# APC1_EPS.net
KiCad netlist of a schematic drawn in Altium Designer
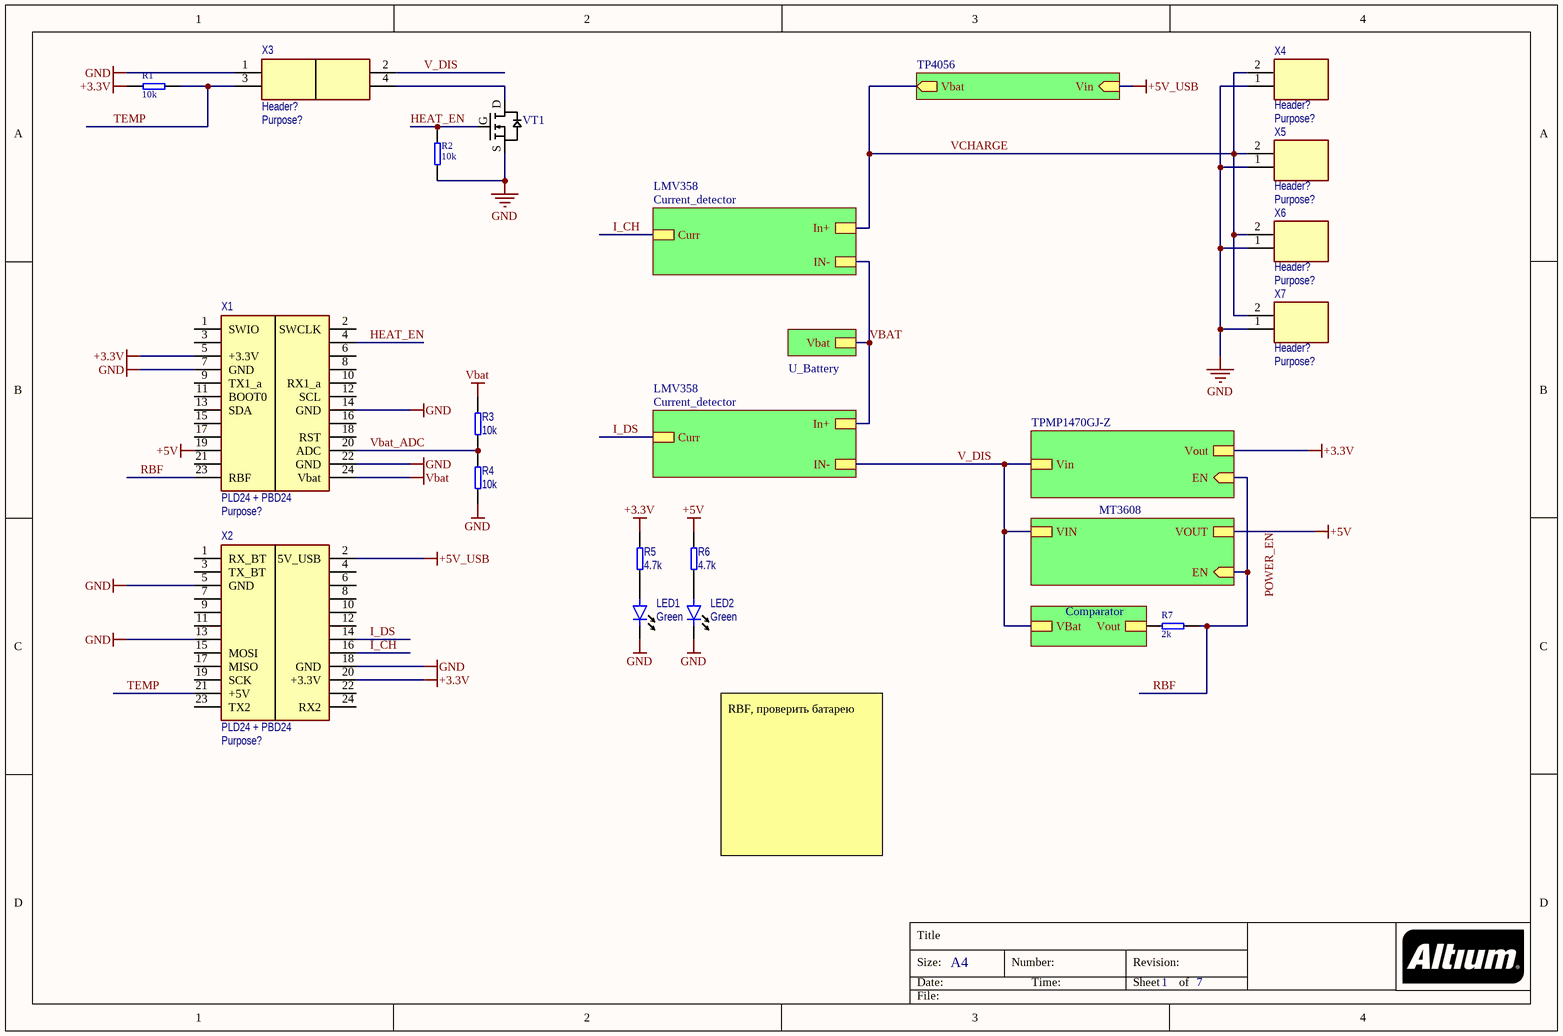
[diagram p0: APC1_EPS.SchDoc]

(export (version "E")
  (design (tool "Eeschema 10.0.6"))
  (components
    (comp (ref "LED1")
      (value "Green")
      (footprint "LED 0603")
      (description "Light Emittering Diode")
      (fields (field (name "Comment") "LED 0603 Green"))
      (libsource (lib "!main") (part "LED"))
    )
    (comp (ref "LED2")
      (value "Green")
      (footprint "LED 0603")
      (description "Light Emittering Diode")
      (fields (field (name "Comment") "LED 0603 Green"))
      (libsource (lib "!main") (part "LED"))
    )
    (comp (ref "R1")
      (value "10k")
      (footprint "RES 0402")
      (description "Resistor")
      (fields (field (name "Comment") "RES 0402 10k"))
      (libsource (lib "!main") (part "!Resistor"))
    )
    (comp (ref "R2")
      (value "10k")
      (footprint "RES 0402")
      (description "Resistor")
      (fields (field (name "Comment") "RES 0402 10k"))
      (libsource (lib "!main") (part "!Resistor"))
    )
    (comp (ref "R3")
      (value "10k")
      (footprint "RES 0402")
      (description "Resistor")
      (fields (field (name "Comment") "RES 0402 10k"))
      (libsource (lib "!main") (part "!Resistor"))
    )
    (comp (ref "R4")
      (value "10k")
      (footprint "RES 0402")
      (description "Resistor")
      (fields (field (name "Comment") "RES 0402 10k"))
      (libsource (lib "!main") (part "!Resistor"))
    )
    (comp (ref "R5")
      (value "4.7k")
      (footprint "RES 0402")
      (description "Resistor")
      (fields (field (name "Comment") "RES 0402 4.7k"))
      (libsource (lib "!main") (part "!Resistor"))
    )
    (comp (ref "R6")
      (value "4.7k")
      (footprint "RES 0402")
      (description "Resistor")
      (fields (field (name "Comment") "RES 0402 4.7k"))
      (libsource (lib "!main") (part "!Resistor"))
    )
    (comp (ref "R7")
      (value "2k")
      (footprint "RES 0402")
      (description "Resistor")
      (fields (field (name "Comment") "RES 0402 2k"))
      (libsource (lib "!main") (part "!Resistor"))
    )
    (comp (ref "VT1")
      (value "AO3400A")
      (footprint "SOT23-3")
      (description "generic N mosfet")
      (libsource (lib "transistors") (part "!Generic N MOSFET"))
    )
    (comp (ref "X1")
      (value "PLD24 + PBD24")
      (footprint "PICOSAT_CNN")
      (description "10x2 header")
      (fields (field (name "PURPOSE") "Purpose?"))
      (libsource (lib "connectors") (part "Header 2x12"))
    )
    (comp (ref "X2")
      (value "PLD24 + PBD24")
      (footprint "PICOSAT_CNN")
      (description "10x2 header")
      (fields (field (name "PURPOSE") "Purpose?"))
      (libsource (lib "connectors") (part "Header 2x12"))
    )
    (comp (ref "X3")
      (value "Header?")
      (footprint "PBD-4-2.54")
      (description "2x2 header")
      (fields (field (name "PURPOSE") "Purpose?"))
      (libsource (lib "connectors") (part "Header 2x2"))
    )
    (comp (ref "X4")
      (value "Header?")
      (footprint "ZH-2")
      (description "2x1 header")
      (fields (field (name "PURPOSE") "Purpose?"))
      (libsource (lib "connectors") (part "Header 1x2"))
    )
    (comp (ref "X5")
      (value "Header?")
      (footprint "ZH-2")
      (description "2x1 header")
      (fields (field (name "PURPOSE") "Purpose?"))
      (libsource (lib "connectors") (part "Header 1x2"))
    )
    (comp (ref "X6")
      (value "Header?")
      (footprint "ZH-2")
      (description "2x1 header")
      (fields (field (name "PURPOSE") "Purpose?"))
      (libsource (lib "connectors") (part "Header 1x2"))
    )
    (comp (ref "X7")
      (value "Header?")
      (footprint "ZH-2")
      (description "2x1 header")
      (fields (field (name "PURPOSE") "Purpose?"))
      (libsource (lib "connectors") (part "Header 1x2"))
    )
  )
  (nets
    (net (code "1") (name "+3.3V") (class "Default")
      (node (ref "R1") (pin "1") (pinfunction "11_1") (pintype "passive"))
      (node (ref "R5") (pin "2") (pinfunction "12_2") (pintype "passive"))
      (node (ref "X1") (pin "5") (pinfunction "+3.3V_5") (pintype "passive"))
      (node (ref "X2") (pin "20") (pinfunction "ADC_20") (pintype "passive"))
    )
    (net (code "2") (name "+5V") (class "Default")
      (node (ref "R6") (pin "2") (pinfunction "12_2") (pintype "passive"))
      (node (ref "X1") (pin "19") (pintype "passive"))
    )
    (net (code "3") (name "+5V_USB") (class "Default")
      (node (ref "X2") (pin "2") (pinfunction "SWCLK_2") (pintype "passive"))
    )
    (net (code "4") (name "/HEAT_EN") (class "Default")
      (node (ref "R2") (pin "2") (pinfunction "12_2") (pintype "passive"))
      (node (ref "VT1") (pin "G2") (pintype "passive"))
      (node (ref "X1") (pin "4") (pintype "passive"))
    )
    (net (code "5") (name "/I_CH") (class "Default") (node (ref "X2") (pin "16") (pintype "passive")))
    (net (code "6") (name "/I_DS") (class "Default")
      (node (ref "X2") (pin "14") (pinfunction "GND_14") (pintype "passive"))
    )
    (net (code "7") (name "/RBF") (class "Default")
      (node (ref "R7") (pin "2") (pinfunction "12_2") (pintype "passive"))
      (node (ref "X1") (pin "23") (pinfunction "RBF_23") (pintype "passive"))
    )
    (net (code "8") (name "/TEMP") (class "Default")
      (node (ref "R1") (pin "2") (pinfunction "12_2") (pintype "passive"))
      (node (ref "X2") (pin "21") (pintype "passive"))
      (node (ref "X3") (pin "3") (pinfunction "6_3") (pintype "passive"))
    )
    (net (code "10") (name "/VCHARGE") (class "Default")
      (node (ref "X4") (pin "2") (pinfunction "2_2") (pintype "passive"))
      (node (ref "X5") (pin "2") (pinfunction "2_2") (pintype "passive"))
      (node (ref "X6") (pin "2") (pinfunction "2_2") (pintype "passive"))
      (node (ref "X7") (pin "2") (pinfunction "2_2") (pintype "passive"))
    )
    (net (code "11") (name "/V_DIS") (class "Default")
      (node (ref "X3") (pin "2") (pinfunction "3_2") (pintype "passive"))
    )
    (net (code "12") (name "/Vbat_ADC") (class "Default")
      (node (ref "R3") (pin "1") (pinfunction "11_1") (pintype "passive"))
      (node (ref "R4") (pin "2") (pinfunction "12_2") (pintype "passive"))
      (node (ref "X1") (pin "20") (pinfunction "ADC_20") (pintype "passive"))
    )
    (net (code "13") (name "/Vout") (class "Default")
      (node (ref "R7") (pin "1") (pinfunction "11_1") (pintype "passive"))
    )
    (net (code "14") (name "GND") (class "Default")
      (node (ref "LED1") (pin "2") (pinfunction "Cathode_2") (pintype "passive"))
      (node (ref "LED2") (pin "2") (pinfunction "Cathode_2") (pintype "passive"))
      (node (ref "R2") (pin "1") (pinfunction "11_1") (pintype "passive"))
      (node (ref "R4") (pin "1") (pinfunction "11_1") (pintype "passive"))
      (node (ref "VT1") (pin "S1") (pintype "passive"))
      (node (ref "X1") (pin "14") (pinfunction "GND_14") (pintype "passive"))
      (node (ref "X1") (pin "22") (pinfunction "GND_22") (pintype "passive"))
      (node (ref "X1") (pin "7") (pinfunction "GND_7") (pintype "passive"))
      (node (ref "X2") (pin "13") (pinfunction "SDA_13") (pintype "passive"))
      (node (ref "X2") (pin "18") (pinfunction "RST_18") (pintype "passive"))
      (node (ref "X2") (pin "5") (pinfunction "+3.3V_5") (pintype "passive"))
      (node (ref "X3") (pin "1") (pinfunction "5_1") (pintype "passive"))
      (node (ref "X4") (pin "1") (pinfunction "1_1") (pintype "passive"))
      (node (ref "X5") (pin "1") (pinfunction "1_1") (pintype "passive"))
      (node (ref "X6") (pin "1") (pinfunction "1_1") (pintype "passive"))
      (node (ref "X7") (pin "1") (pinfunction "1_1") (pintype "passive"))
    )
    (net (code "15") (name "Net-(LED1-Anode)") (class "Default")
      (node (ref "LED1") (pin "1") (pinfunction "Anode_1") (pintype "passive"))
      (node (ref "R5") (pin "1") (pinfunction "11_1") (pintype "passive"))
    )
    (net (code "16") (name "Net-(LED2-Anode)") (class "Default")
      (node (ref "LED2") (pin "1") (pinfunction "Anode_1") (pintype "passive"))
      (node (ref "R6") (pin "1") (pinfunction "11_1") (pintype "passive"))
    )
    (net (code "17") (name "Net-(VT1-PadD6)") (class "Default")
      (node (ref "VT1") (pin "D6") (pintype "passive"))
      (node (ref "X3") (pin "4") (pinfunction "4_4") (pintype "passive"))
    )
    (net (code "18") (name "Vbat") (class "Default")
      (node (ref "R3") (pin "2") (pinfunction "12_2") (pintype "passive"))
      (node (ref "X1") (pin "24") (pinfunction "Vbat_24") (pintype "passive"))
    )
    (net (code "19") (name "unconnected-(X1-BOOT0-Pad11)") (class "Default")
      (node (ref "X1") (pin "11") (pinfunction "BOOT0_11") (pintype "passive"))
    )
    (net (code "20") (name "unconnected-(X1-Pad3)") (class "Default")
      (node (ref "X1") (pin "3") (pintype "passive"))
    )
    (net (code "21") (name "unconnected-(X1-Pad6)") (class "Default")
      (node (ref "X1") (pin "6") (pintype "passive"))
    )
    (net (code "22") (name "unconnected-(X1-Pad8)") (class "Default")
      (node (ref "X1") (pin "8") (pintype "passive"))
    )
    (net (code "23") (name "unconnected-(X1-Pad15)") (class "Default")
      (node (ref "X1") (pin "15") (pintype "passive"))
    )
    (net (code "24") (name "unconnected-(X1-Pad16)") (class "Default")
      (node (ref "X1") (pin "16") (pintype "passive"))
    )
    (net (code "25") (name "unconnected-(X1-Pad17)") (class "Default")
      (node (ref "X1") (pin "17") (pintype "passive"))
    )
    (net (code "26") (name "unconnected-(X1-Pad21)") (class "Default")
      (node (ref "X1") (pin "21") (pintype "passive"))
    )
    (net (code "27") (name "unconnected-(X1-RST-Pad18)") (class "Default")
      (node (ref "X1") (pin "18") (pinfunction "RST_18") (pintype "passive"))
    )
    (net (code "28") (name "unconnected-(X1-RX1_a-Pad10)") (class "Default")
      (node (ref "X1") (pin "10") (pinfunction "RX1_a_10") (pintype "passive"))
    )
    (net (code "29") (name "unconnected-(X1-SCL-Pad12)") (class "Default")
      (node (ref "X1") (pin "12") (pinfunction "SCL_12") (pintype "passive"))
    )
    (net (code "30") (name "unconnected-(X1-SDA-Pad13)") (class "Default")
      (node (ref "X1") (pin "13") (pinfunction "SDA_13") (pintype "passive"))
    )
    (net (code "31") (name "unconnected-(X1-SWCLK-Pad2)") (class "Default")
      (node (ref "X1") (pin "2") (pinfunction "SWCLK_2") (pintype "passive"))
    )
    (net (code "32") (name "unconnected-(X1-SWIO-Pad1)") (class "Default")
      (node (ref "X1") (pin "1") (pinfunction "SWIO_1") (pintype "passive"))
    )
    (net (code "33") (name "unconnected-(X1-TX1_a-Pad9)") (class "Default")
      (node (ref "X1") (pin "9") (pinfunction "TX1_a_9") (pintype "passive"))
    )
    (net (code "34") (name "unconnected-(X2-BOOT0-Pad11)") (class "Default")
      (node (ref "X2") (pin "11") (pinfunction "BOOT0_11") (pintype "passive"))
    )
    (net (code "35") (name "unconnected-(X2-GND-Pad7)") (class "Default")
      (node (ref "X2") (pin "7") (pinfunction "GND_7") (pintype "passive"))
    )
    (net (code "36") (name "unconnected-(X2-GND-Pad22)") (class "Default")
      (node (ref "X2") (pin "22") (pinfunction "GND_22") (pintype "passive"))
    )
    (net (code "37") (name "unconnected-(X2-Pad3)") (class "Default")
      (node (ref "X2") (pin "3") (pintype "passive"))
    )
    (net (code "38") (name "unconnected-(X2-Pad4)") (class "Default")
      (node (ref "X2") (pin "4") (pintype "passive"))
    )
    (net (code "39") (name "unconnected-(X2-Pad6)") (class "Default")
      (node (ref "X2") (pin "6") (pintype "passive"))
    )
    (net (code "40") (name "unconnected-(X2-Pad8)") (class "Default")
      (node (ref "X2") (pin "8") (pintype "passive"))
    )
    (net (code "41") (name "unconnected-(X2-Pad15)") (class "Default")
      (node (ref "X2") (pin "15") (pintype "passive"))
    )
    (net (code "42") (name "unconnected-(X2-Pad17)") (class "Default")
      (node (ref "X2") (pin "17") (pintype "passive"))
    )
    (net (code "43") (name "unconnected-(X2-Pad19)") (class "Default")
      (node (ref "X2") (pin "19") (pintype "passive"))
    )
    (net (code "44") (name "unconnected-(X2-RBF-Pad23)") (class "Default")
      (node (ref "X2") (pin "23") (pinfunction "RBF_23") (pintype "passive"))
    )
    (net (code "45") (name "unconnected-(X2-RX1_a-Pad10)") (class "Default")
      (node (ref "X2") (pin "10") (pinfunction "RX1_a_10") (pintype "passive"))
    )
    (net (code "46") (name "unconnected-(X2-SCL-Pad12)") (class "Default")
      (node (ref "X2") (pin "12") (pinfunction "SCL_12") (pintype "passive"))
    )
    (net (code "47") (name "unconnected-(X2-SWIO-Pad1)") (class "Default")
      (node (ref "X2") (pin "1") (pinfunction "SWIO_1") (pintype "passive"))
    )
    (net (code "48") (name "unconnected-(X2-TX1_a-Pad9)") (class "Default")
      (node (ref "X2") (pin "9") (pinfunction "TX1_a_9") (pintype "passive"))
    )
    (net (code "49") (name "unconnected-(X2-Vbat-Pad24)") (class "Default")
      (node (ref "X2") (pin "24") (pinfunction "Vbat_24") (pintype "passive"))
    )
  )
)
